# T_STorM32_motor_v25E-sq.net
KiCad netlist of a schematic drawn in EAGLE
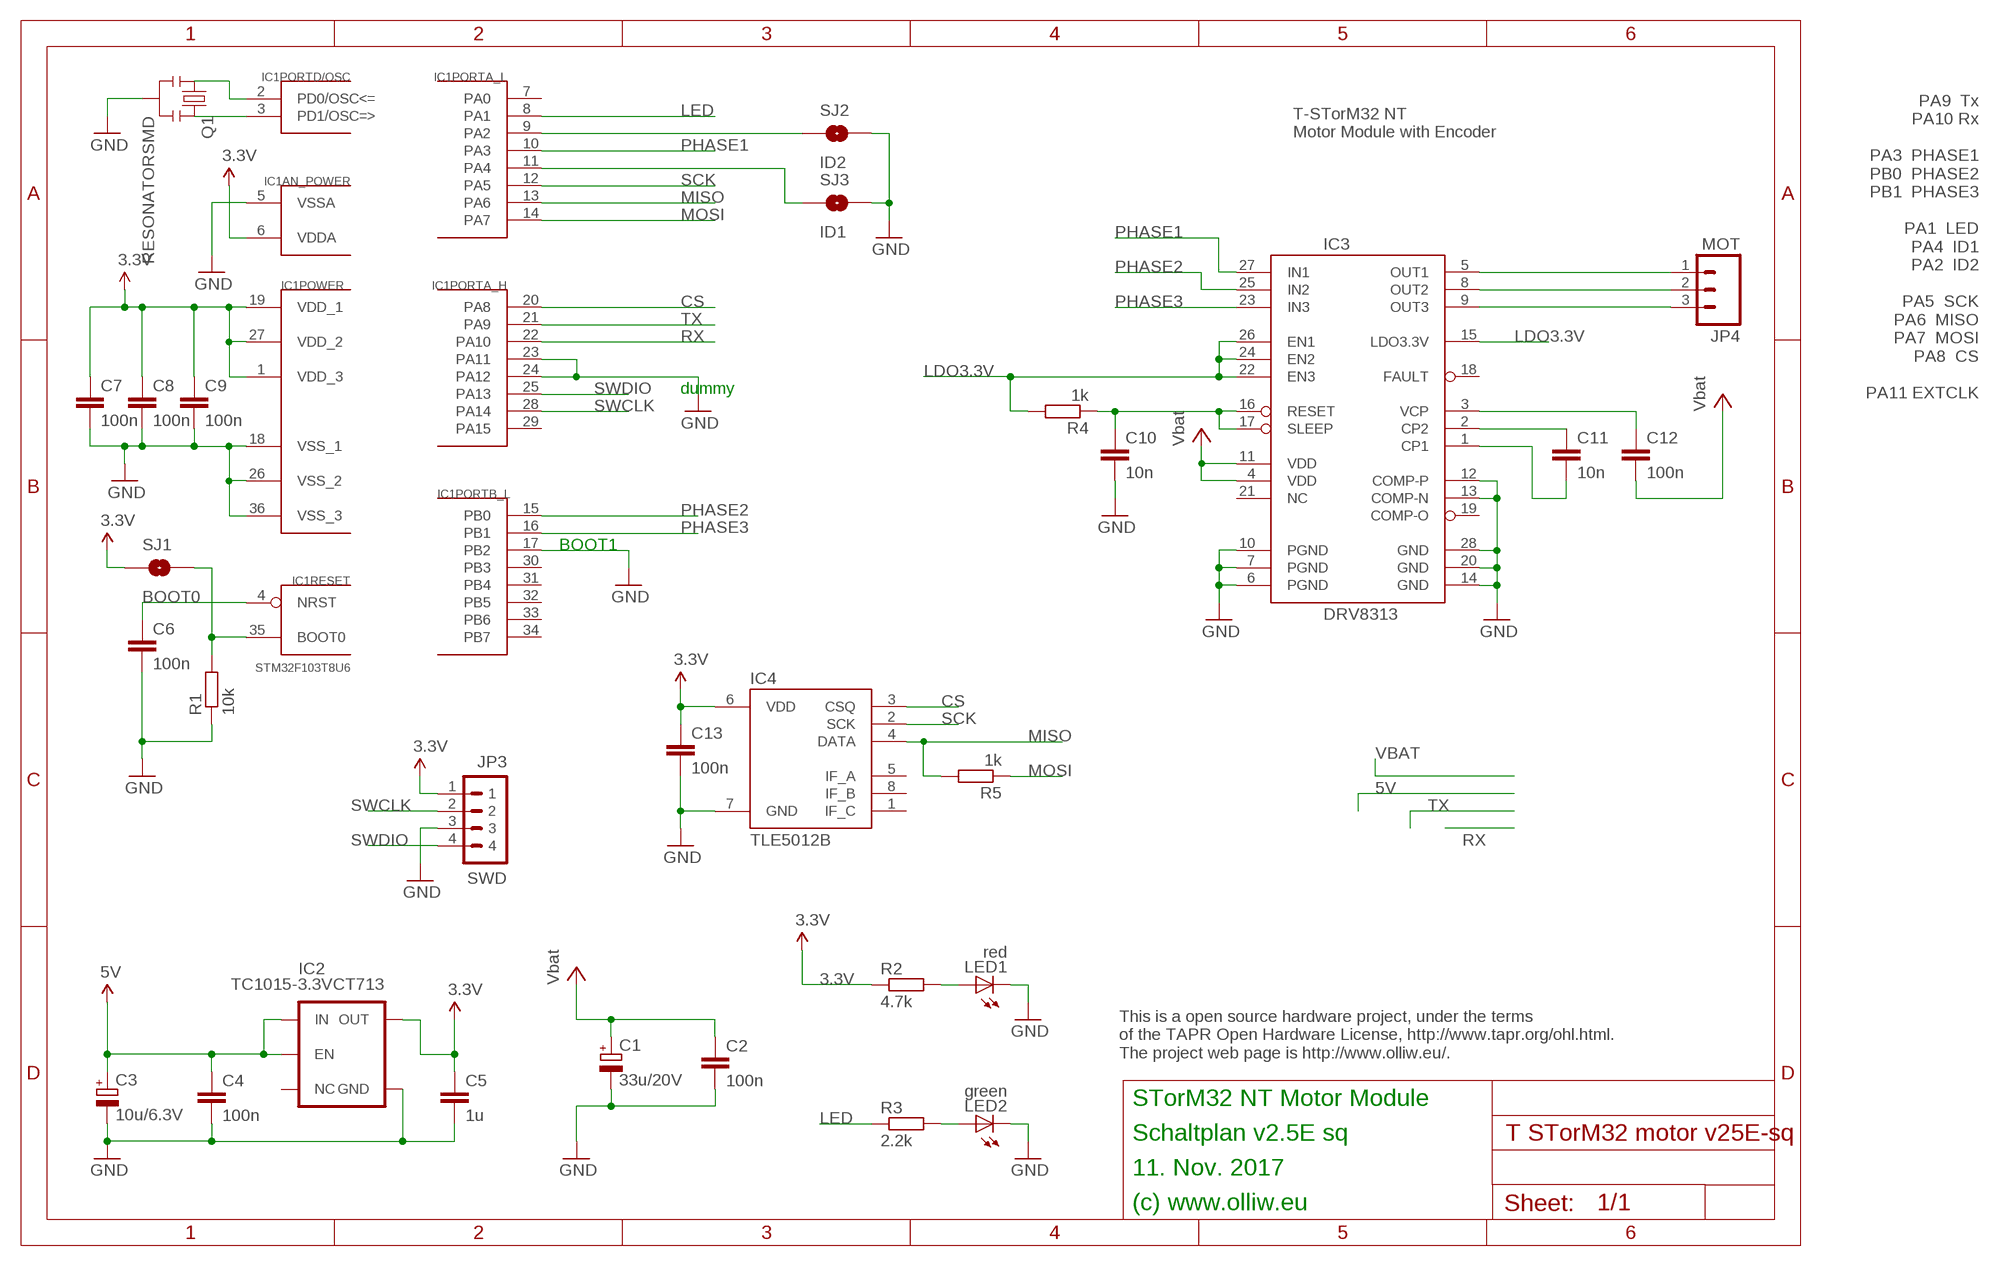
[diagram p0: schematic, sheet 1]

(export (version "E")
  (design (tool "Eeschema 10.0.6"))
  (components
    (comp (ref "C1")
      (value "33u/20V")
      (footprint "eagle-import:SMC_C")
      (libsource (lib "eagle-import") (part "CPOL-EUSMCC"))
    )
    (comp (ref "C2")
      (value "100n")
      (footprint "eagle-import:C0603")
      (libsource (lib "eagle-import") (part "C-EUC0603"))
    )
    (comp (ref "C3")
      (value "10u/6.3V")
      (footprint "eagle-import:SMC_B")
      (libsource (lib "eagle-import") (part "CPOL-EUSMCB"))
    )
    (comp (ref "C4")
      (value "100n")
      (footprint "eagle-import:C0603")
      (libsource (lib "eagle-import") (part "C-EUC0603"))
    )
    (comp (ref "C5")
      (value "1u")
      (footprint "eagle-import:C0603")
      (libsource (lib "eagle-import") (part "C-EUC0603"))
    )
    (comp (ref "C6")
      (value "100n")
      (footprint "eagle-import:C0603")
      (libsource (lib "eagle-import") (part "C-EUC0603"))
    )
    (comp (ref "C7")
      (value "100n")
      (footprint "eagle-import:C0603")
      (libsource (lib "eagle-import") (part "C-EUC0603"))
    )
    (comp (ref "C8")
      (value "100n")
      (footprint "eagle-import:C0603")
      (libsource (lib "eagle-import") (part "C-EUC0603"))
    )
    (comp (ref "C9")
      (value "100n")
      (footprint "eagle-import:C0603")
      (libsource (lib "eagle-import") (part "C-EUC0603"))
    )
    (comp (ref "C10")
      (value "10n")
      (footprint "eagle-import:C0603")
      (libsource (lib "eagle-import") (part "C-EUC0603"))
    )
    (comp (ref "C11")
      (value "10n")
      (footprint "eagle-import:C0603")
      (libsource (lib "eagle-import") (part "C-EUC0603"))
    )
    (comp (ref "C12")
      (value "100n")
      (footprint "eagle-import:C0603")
      (libsource (lib "eagle-import") (part "C-EUC0603"))
    )
    (comp (ref "C13")
      (value "100n")
      (footprint "eagle-import:C0603")
      (libsource (lib "eagle-import") (part "C-EUC0603"))
    )
    (comp (ref "IC1")
      (value "STM32F103T8U6")
      (footprint "eagle-import:VFQFPN36")
      (libsource (lib "eagle-import") (part "STM32F10XTXU6"))
    )
    (comp (ref "IC2")
      (value "TC1015-3.3VCT713")
      (footprint "eagle-import:SOT23-5")
      (libsource (lib "eagle-import") (part "V_REG_TPS76433SOT23-5"))
    )
    (comp (ref "IC3")
      (value "DRV8313")
      (footprint "eagle-import:HTSSOP28")
      (libsource (lib "eagle-import") (part "DRV8313"))
    )
    (comp (ref "IC4")
      (value "TLE5012B")
      (footprint "eagle-import:SO08")
      (libsource (lib "eagle-import") (part "TLE5012B"))
    )
    (comp (ref "JP3")
      (value "SWD")
      (footprint "eagle-import:4X1_1P27_OCT_BILEX")
      (libsource (lib "eagle-import") (part "P4X1_1P27-OCT_BILEX"))
    )
    (comp (ref "JP4")
      (value "MOT")
      (footprint "eagle-import:1X03_NO_SILK")
      (libsource (lib "eagle-import") (part "M031X03_NO_SILK"))
    )
    (comp (ref "LED1")
      (value "red")
      (footprint "eagle-import:CHIPLED_0603")
      (libsource (lib "eagle-import") (part "LEDCHIPLED_0603"))
    )
    (comp (ref "LED2")
      (value "green")
      (footprint "eagle-import:CHIPLED_0603")
      (libsource (lib "eagle-import") (part "LEDCHIPLED_0603"))
    )
    (comp (ref "Q1")
      (value "RESONATORSMD")
      (footprint "eagle-import:RESONATOR-SMD")
      (libsource (lib "eagle-import") (part "RESONATORSMD"))
    )
    (comp (ref "R1")
      (value "10k")
      (footprint "eagle-import:R0603")
      (libsource (lib "eagle-import") (part "R-EU_R0603"))
    )
    (comp (ref "R2")
      (value "4.7k")
      (footprint "eagle-import:R0603")
      (libsource (lib "eagle-import") (part "R-EU_R0603"))
    )
    (comp (ref "R3")
      (value "2.2k")
      (footprint "eagle-import:R0603")
      (libsource (lib "eagle-import") (part "R-EU_R0603"))
    )
    (comp (ref "R4")
      (value "1k")
      (footprint "eagle-import:R0603")
      (libsource (lib "eagle-import") (part "R-EU_R0603"))
    )
    (comp (ref "R5")
      (value "1k")
      (footprint "eagle-import:R0603")
      (libsource (lib "eagle-import") (part "R-EU_R0603"))
    )
    (comp (ref "SJ1")
      (value "BOOT0")
      (footprint "eagle-import:SJ_2S-NO")
      (libsource (lib "eagle-import") (part "SOLDERJUMPERNO"))
    )
    (comp (ref "SJ2")
      (value "ID2")
      (footprint "eagle-import:SJ_2S-NO")
      (libsource (lib "eagle-import") (part "SOLDERJUMPERNO"))
    )
    (comp (ref "SJ3")
      (value "ID1")
      (footprint "eagle-import:SJ_2S-NO")
      (libsource (lib "eagle-import") (part "SOLDERJUMPERNO"))
    )
  )
  (nets
    (net (code "1") (name "/CS") (class "Default")
      (node (ref "IC1") (pin "20") (pinfunction "PA8_20") (pintype "bidirectional"))
      (node (ref "IC4") (pin "3") (pinfunction "CSQ_3") (pintype "input"))
    )
    (net (code "2") (name "/LDO3.3V") (class "Default")
      (node (ref "IC3") (pin "15") (pinfunction "LDO3.3V_15") (pintype "output"))
      (node (ref "IC3") (pin "22") (pinfunction "EN3_22") (pintype "input"))
      (node (ref "IC3") (pin "24") (pinfunction "EN2_24") (pintype "input"))
      (node (ref "IC3") (pin "26") (pinfunction "EN1_26") (pintype "input"))
      (node (ref "R4") (pin "2") (pinfunction "2_2") (pintype "passive"))
    )
    (net (code "3") (name "/LED") (class "Default")
      (node (ref "IC1") (pin "8") (pinfunction "PA1_8") (pintype "bidirectional"))
      (node (ref "R3") (pin "1") (pinfunction "1_1") (pintype "passive"))
    )
    (net (code "4") (name "/MISO") (class "Default")
      (node (ref "IC1") (pin "13") (pinfunction "PA6_13") (pintype "bidirectional"))
      (node (ref "IC4") (pin "4") (pinfunction "DATA_4") (pintype "bidirectional"))
      (node (ref "R5") (pin "2") (pinfunction "2_2") (pintype "passive"))
    )
    (net (code "5") (name "/MOSI") (class "Default")
      (node (ref "IC1") (pin "14") (pinfunction "PA7_14") (pintype "bidirectional"))
      (node (ref "R5") (pin "1") (pinfunction "1_1") (pintype "passive"))
    )
    (net (code "6") (name "/PHASE1") (class "Default")
      (node (ref "IC1") (pin "10") (pinfunction "PA3_10") (pintype "bidirectional"))
      (node (ref "IC3") (pin "27") (pinfunction "IN1_27") (pintype "input"))
    )
    (net (code "7") (name "/PHASE2") (class "Default")
      (node (ref "IC1") (pin "15") (pinfunction "PB0_15") (pintype "bidirectional"))
      (node (ref "IC3") (pin "25") (pinfunction "IN2_25") (pintype "input"))
    )
    (net (code "8") (name "/PHASE3") (class "Default")
      (node (ref "IC1") (pin "16") (pinfunction "PB1_16") (pintype "bidirectional"))
      (node (ref "IC3") (pin "23") (pinfunction "IN3_23") (pintype "input"))
    )
    (net (code "9") (name "/RX") (class "Default")
      (node (ref "IC1") (pin "22") (pinfunction "PA10_22") (pintype "bidirectional"))
    )
    (net (code "10") (name "/SCK") (class "Default")
      (node (ref "IC1") (pin "12") (pinfunction "PA5_12") (pintype "bidirectional"))
      (node (ref "IC4") (pin "2") (pinfunction "SCK_2") (pintype "input"))
    )
    (net (code "11") (name "/SWCLK") (class "Default")
      (node (ref "IC1") (pin "28") (pinfunction "PA14_28") (pintype "bidirectional"))
      (node (ref "JP3") (pin "2") (pinfunction "2_2") (pintype "passive"))
    )
    (net (code "12") (name "/SWDIO") (class "Default")
      (node (ref "IC1") (pin "25") (pinfunction "PA13_25") (pintype "bidirectional"))
      (node (ref "JP3") (pin "4") (pinfunction "4_4") (pintype "passive"))
    )
    (net (code "13") (name "/TX") (class "Default")
      (node (ref "IC1") (pin "21") (pinfunction "PA9_21") (pintype "bidirectional"))
    )
    (net (code "14") (name "3.3V") (class "Default")
      (node (ref "C13") (pin "1") (pinfunction "1_1") (pintype "passive"))
      (node (ref "C5") (pin "1") (pinfunction "1_1") (pintype "passive"))
      (node (ref "C7") (pin "1") (pinfunction "1_1") (pintype "passive"))
      (node (ref "C8") (pin "1") (pinfunction "1_1") (pintype "passive"))
      (node (ref "C9") (pin "1") (pinfunction "1_1") (pintype "passive"))
      (node (ref "IC1") (pin "1") (pinfunction "VDD_3_1") (pintype "power_in"))
      (node (ref "IC1") (pin "19") (pinfunction "VDD_1_19") (pintype "power_in"))
      (node (ref "IC1") (pin "27") (pinfunction "VDD_2_27") (pintype "power_in"))
      (node (ref "IC1") (pin "6") (pinfunction "VDDA_6") (pintype "power_in"))
      (node (ref "IC2") (pin "5") (pinfunction "OUT_5") (pintype "passive"))
      (node (ref "IC4") (pin "6") (pinfunction "VDD_6") (pintype "power_in"))
      (node (ref "JP3") (pin "1") (pinfunction "1_1") (pintype "passive"))
      (node (ref "R2") (pin "1") (pinfunction "1_1") (pintype "passive"))
      (node (ref "SJ1") (pin "1") (pinfunction "1_1") (pintype "passive"))
    )
    (net (code "15") (name "5V") (class "Default")
      (node (ref "C3") (pin "+") (pinfunction "+_+") (pintype "passive"))
      (node (ref "C4") (pin "1") (pinfunction "1_1") (pintype "passive"))
      (node (ref "IC2") (pin "1") (pinfunction "IN_1") (pintype "input"))
      (node (ref "IC2") (pin "3") (pinfunction "EN_3") (pintype "input"))
    )
    (net (code "16") (name "GND") (class "Default")
      (node (ref "C1") (pin "-") (pinfunction "-_-") (pintype "passive"))
      (node (ref "C10") (pin "2") (pinfunction "2_2") (pintype "passive"))
      (node (ref "C13") (pin "2") (pinfunction "2_2") (pintype "passive"))
      (node (ref "C2") (pin "2") (pinfunction "2_2") (pintype "passive"))
      (node (ref "C3") (pin "-") (pinfunction "-_-") (pintype "passive"))
      (node (ref "C4") (pin "2") (pinfunction "2_2") (pintype "passive"))
      (node (ref "C5") (pin "2") (pinfunction "2_2") (pintype "passive"))
      (node (ref "C6") (pin "2") (pinfunction "2_2") (pintype "passive"))
      (node (ref "C7") (pin "2") (pinfunction "2_2") (pintype "passive"))
      (node (ref "C8") (pin "2") (pinfunction "2_2") (pintype "passive"))
      (node (ref "C9") (pin "2") (pinfunction "2_2") (pintype "passive"))
      (node (ref "IC1") (pin "17") (pinfunction "PB2_17") (pintype "bidirectional"))
      (node (ref "IC1") (pin "18") (pinfunction "VSS_1_18") (pintype "power_in"))
      (node (ref "IC1") (pin "23") (pinfunction "PA11_23") (pintype "bidirectional"))
      (node (ref "IC1") (pin "24") (pinfunction "PA12_24") (pintype "bidirectional"))
      (node (ref "IC1") (pin "26") (pinfunction "VSS_2_26") (pintype "power_in"))
      (node (ref "IC1") (pin "36") (pinfunction "VSS_3_36") (pintype "power_in"))
      (node (ref "IC1") (pin "5") (pinfunction "VSSA_5") (pintype "power_in"))
      (node (ref "IC2") (pin "2") (pinfunction "GND_2") (pintype "input"))
      (node (ref "IC3") (pin "10") (pinfunction "PGND_10") (pintype "power_in"))
      (node (ref "IC3") (pin "12") (pinfunction "COMP-P_12") (pintype "input"))
      (node (ref "IC3") (pin "13") (pinfunction "COMP-N_13") (pintype "input"))
      (node (ref "IC3") (pin "14") (pinfunction "GND_14") (pintype "power_in"))
      (node (ref "IC3") (pin "20") (pinfunction "GND_20") (pintype "power_in"))
      (node (ref "IC3") (pin "28") (pinfunction "GND_28") (pintype "power_in"))
      (node (ref "IC3") (pin "6") (pinfunction "PGND_6") (pintype "power_in"))
      (node (ref "IC3") (pin "7") (pinfunction "PGND_7") (pintype "power_in"))
      (node (ref "IC4") (pin "7") (pinfunction "GND_7") (pintype "power_in"))
      (node (ref "JP3") (pin "3") (pinfunction "3_3") (pintype "passive"))
      (node (ref "LED1") (pin "C") (pinfunction "C_C") (pintype "passive"))
      (node (ref "LED2") (pin "C") (pinfunction "C_C") (pintype "passive"))
      (node (ref "Q1") (pin "2") (pinfunction "2_2") (pintype "passive"))
      (node (ref "R1") (pin "1") (pinfunction "1_1") (pintype "passive"))
      (node (ref "SJ2") (pin "2") (pinfunction "2_2") (pintype "passive"))
      (node (ref "SJ3") (pin "2") (pinfunction "2_2") (pintype "passive"))
    )
    (net (code "17") (name "Net-(IC1C-PA2)") (class "Default")
      (node (ref "IC1") (pin "9") (pinfunction "PA2_9") (pintype "bidirectional"))
      (node (ref "SJ2") (pin "1") (pinfunction "1_1") (pintype "passive"))
    )
    (net (code "18") (name "Net-(IC1C-PA4)") (class "Default")
      (node (ref "IC1") (pin "11") (pinfunction "PA4_11") (pintype "bidirectional"))
      (node (ref "SJ3") (pin "1") (pinfunction "1_1") (pintype "passive"))
    )
    (net (code "19") (name "Net-(IC1E-PD0{slash}OSC<=)") (class "Default")
      (node (ref "IC1") (pin "2") (pinfunction "PD0/OSC<=_2") (pintype "bidirectional"))
      (node (ref "Q1") (pin "1") (pinfunction "1_1") (pintype "passive"))
    )
    (net (code "20") (name "Net-(IC1E-PD1{slash}OSC=>)") (class "Default")
      (node (ref "IC1") (pin "3") (pinfunction "PD1/OSC=>_3") (pintype "bidirectional"))
      (node (ref "Q1") (pin "3") (pinfunction "3_3") (pintype "passive"))
    )
    (net (code "21") (name "Net-(IC1G-BOOT0)") (class "Default")
      (node (ref "IC1") (pin "35") (pinfunction "BOOT0_35") (pintype "input"))
      (node (ref "R1") (pin "2") (pinfunction "2_2") (pintype "passive"))
      (node (ref "SJ1") (pin "2") (pinfunction "2_2") (pintype "passive"))
    )
    (net (code "22") (name "Net-(IC1G-NRST)") (class "Default")
      (node (ref "C6") (pin "1") (pinfunction "1_1") (pintype "passive"))
      (node (ref "IC1") (pin "4") (pinfunction "NRST_4") (pintype "input"))
    )
    (net (code "23") (name "Net-(IC3-CP1)") (class "Default")
      (node (ref "C11") (pin "2") (pinfunction "2_2") (pintype "passive"))
      (node (ref "IC3") (pin "1") (pinfunction "CP1_1") (pintype "bidirectional"))
    )
    (net (code "24") (name "Net-(IC3-CP2)") (class "Default")
      (node (ref "C11") (pin "1") (pinfunction "1_1") (pintype "passive"))
      (node (ref "IC3") (pin "2") (pinfunction "CP2_2") (pintype "bidirectional"))
    )
    (net (code "25") (name "Net-(IC3-OUT1)") (class "Default")
      (node (ref "IC3") (pin "5") (pinfunction "OUT1_5") (pintype "output"))
      (node (ref "JP4") (pin "1") (pinfunction "1_1") (pintype "passive"))
    )
    (net (code "26") (name "Net-(IC3-OUT2)") (class "Default")
      (node (ref "IC3") (pin "8") (pinfunction "OUT2_8") (pintype "output"))
      (node (ref "JP4") (pin "2") (pinfunction "2_2") (pintype "passive"))
    )
    (net (code "27") (name "Net-(IC3-OUT3)") (class "Default")
      (node (ref "IC3") (pin "9") (pinfunction "OUT3_9") (pintype "output"))
      (node (ref "JP4") (pin "3") (pinfunction "3_3") (pintype "passive"))
    )
    (net (code "28") (name "Net-(IC3-RESET)") (class "Default")
      (node (ref "C10") (pin "1") (pinfunction "1_1") (pintype "passive"))
      (node (ref "IC3") (pin "16") (pinfunction "RESET_16") (pintype "input"))
      (node (ref "IC3") (pin "17") (pinfunction "SLEEP_17") (pintype "input"))
      (node (ref "R4") (pin "1") (pinfunction "1_1") (pintype "passive"))
    )
    (net (code "29") (name "Net-(IC3-VCP)") (class "Default")
      (node (ref "C12") (pin "1") (pinfunction "1_1") (pintype "passive"))
      (node (ref "IC3") (pin "3") (pinfunction "VCP_3") (pintype "bidirectional"))
    )
    (net (code "30") (name "Net-(LED1-PadA)") (class "Default")
      (node (ref "LED1") (pin "A") (pinfunction "A_A") (pintype "passive"))
      (node (ref "R2") (pin "2") (pinfunction "2_2") (pintype "passive"))
    )
    (net (code "31") (name "Net-(LED2-PadA)") (class "Default")
      (node (ref "LED2") (pin "A") (pinfunction "A_A") (pintype "passive"))
      (node (ref "R3") (pin "2") (pinfunction "2_2") (pintype "passive"))
    )
    (net (code "32") (name "Vbat") (class "Default")
      (node (ref "C1") (pin "+") (pinfunction "+_+") (pintype "passive"))
      (node (ref "C12") (pin "2") (pinfunction "2_2") (pintype "passive"))
      (node (ref "C2") (pin "1") (pinfunction "1_1") (pintype "passive"))
      (node (ref "IC3") (pin "11") (pinfunction "VDD_11") (pintype "power_in"))
      (node (ref "IC3") (pin "4") (pinfunction "VDD_4") (pintype "power_in"))
    )
    (net (code "33") (name "unconnected-(IC1B-PA15-Pad29)") (class "Default")
      (node (ref "IC1") (pin "29") (pinfunction "PA15_29") (pintype "bidirectional"))
    )
    (net (code "34") (name "unconnected-(IC1C-PA0-Pad7)") (class "Default")
      (node (ref "IC1") (pin "7") (pinfunction "PA0_7") (pintype "bidirectional"))
    )
    (net (code "35") (name "unconnected-(IC1D-PB3-Pad30)") (class "Default")
      (node (ref "IC1") (pin "30") (pinfunction "PB3_30") (pintype "bidirectional"))
    )
    (net (code "36") (name "unconnected-(IC1D-PB4-Pad31)") (class "Default")
      (node (ref "IC1") (pin "31") (pinfunction "PB4_31") (pintype "bidirectional"))
    )
    (net (code "37") (name "unconnected-(IC1D-PB5-Pad32)") (class "Default")
      (node (ref "IC1") (pin "32") (pinfunction "PB5_32") (pintype "bidirectional"))
    )
    (net (code "38") (name "unconnected-(IC1D-PB6-Pad33)") (class "Default")
      (node (ref "IC1") (pin "33") (pinfunction "PB6_33") (pintype "bidirectional"))
    )
    (net (code "39") (name "unconnected-(IC1D-PB7-Pad34)") (class "Default")
      (node (ref "IC1") (pin "34") (pinfunction "PB7_34") (pintype "bidirectional"))
    )
    (net (code "40") (name "unconnected-(IC2-NC-Pad4)") (class "Default")
      (node (ref "IC2") (pin "4") (pinfunction "NC_4") (pintype "input"))
    )
    (net (code "41") (name "unconnected-(IC3-COMP-O-Pad19)") (class "Default")
      (node (ref "IC3") (pin "19") (pinfunction "COMP-O_19") (pintype "output"))
    )
    (net (code "42") (name "unconnected-(IC3-FAULT-Pad18)") (class "Default")
      (node (ref "IC3") (pin "18") (pinfunction "FAULT_18") (pintype "output"))
    )
    (net (code "43") (name "unconnected-(IC3-NC-Pad21)") (class "Default")
      (node (ref "IC3") (pin "21") (pinfunction "NC_21") (pintype "no_connect"))
    )
    (net (code "44") (name "unconnected-(IC4-IF_A-Pad5)") (class "Default")
      (node (ref "IC4") (pin "5") (pinfunction "IF_A_5") (pintype "bidirectional"))
    )
    (net (code "45") (name "unconnected-(IC4-IF_B-Pad8)") (class "Default")
      (node (ref "IC4") (pin "8") (pinfunction "IF_B_8") (pintype "output"))
    )
    (net (code "46") (name "unconnected-(IC4-IF_C-Pad1)") (class "Default")
      (node (ref "IC4") (pin "1") (pinfunction "IF_C_1") (pintype "bidirectional"))
    )
  )
)
